# SCH_Schematic-PCB-FC-TD_2026-05-04.net
KiCad netlist of a schematic drawn in EasyEDA
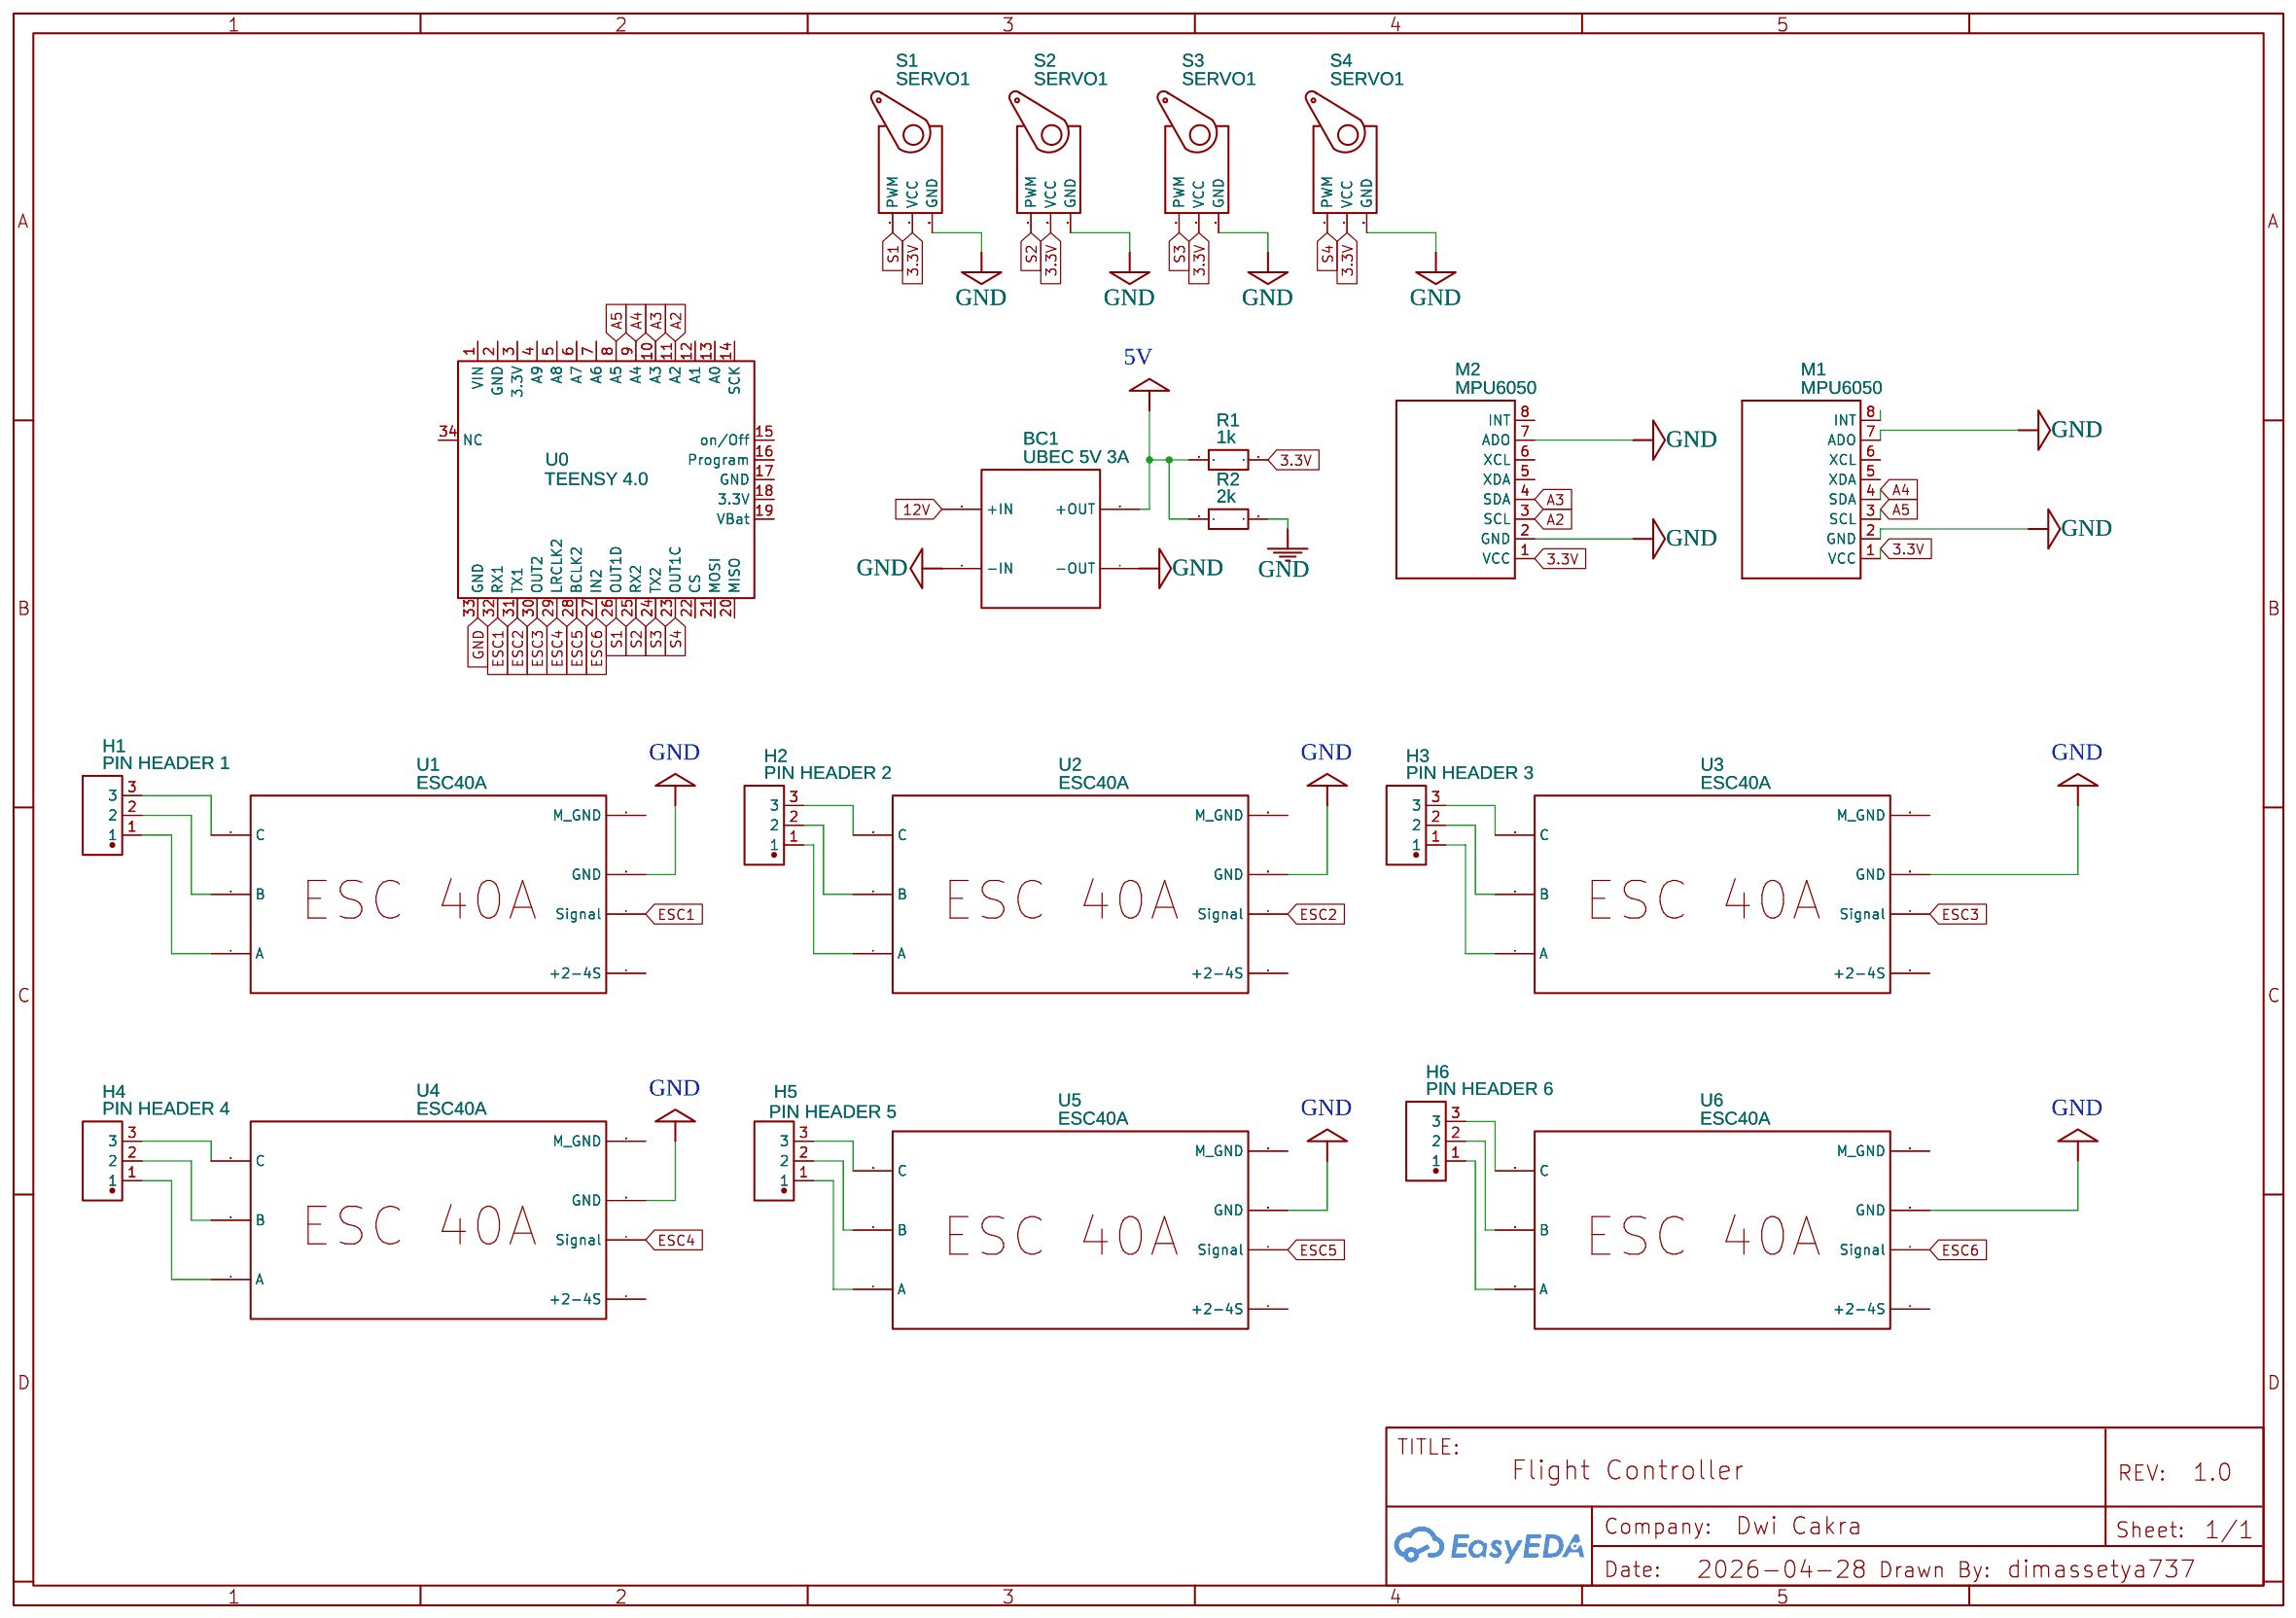
[diagram p0: schematic sheet]

(export (version "E")
  (design (tool "Eeschema 10.0.6"))
  (components
    (comp (ref "BC1") (value "UBEC 5V 3A") (libsource (lib "") (part "UBEC 5V 3A")))
    (comp (ref "H1")
      (value "PIN HEADER 1")
      (fields
        (field (name "Manufacturer Part") "HX PH254-01-03-Z-L11.5 pcb pin header")
        (field (name "Manufacturer") "hanxia(韩下)")
      )
      (libsource (lib "") (part "HX PH254-01-03-Z-L11.5 PCB PIN HEADER"))
    )
    (comp (ref "H2")
      (value "PIN HEADER 2")
      (fields
        (field (name "Manufacturer Part") "HX PH254-01-03-Z-L11.5 pcb pin header")
        (field (name "Manufacturer") "hanxia(韩下)")
      )
      (libsource (lib "") (part "HX PH254-01-03-Z-L11.5 PCB PIN HEADER"))
    )
    (comp (ref "H3")
      (value "PIN HEADER 3")
      (fields
        (field (name "Manufacturer Part") "HX PH254-01-03-Z-L11.5 pcb pin header")
        (field (name "Manufacturer") "hanxia(韩下)")
      )
      (libsource (lib "") (part "HX PH254-01-03-Z-L11.5 PCB PIN HEADER"))
    )
    (comp (ref "H4")
      (value "PIN HEADER 4")
      (fields
        (field (name "Manufacturer Part") "HX PH254-01-03-Z-L11.5 pcb pin header")
        (field (name "Manufacturer") "hanxia(韩下)")
      )
      (libsource (lib "") (part "HX PH254-01-03-Z-L11.5 PCB PIN HEADER"))
    )
    (comp (ref "H5")
      (value "PIN HEADER 5")
      (fields
        (field (name "Manufacturer Part") "HX PH254-01-03-Z-L11.5 pcb pin header")
        (field (name "Manufacturer") "hanxia(韩下)")
      )
      (libsource (lib "") (part "HX PH254-01-03-Z-L11.5 PCB PIN HEADER"))
    )
    (comp (ref "H6")
      (value "PIN HEADER 6")
      (fields
        (field (name "Manufacturer Part") "HX PH254-01-03-Z-L11.5 pcb pin header")
        (field (name "Manufacturer") "hanxia(韩下)")
      )
      (libsource (lib "") (part "HX PH254-01-03-Z-L11.5 PCB PIN HEADER"))
    )
    (comp (ref "M1") (value "MPU6050") (libsource (lib "") (part "MPU6050")))
    (comp (ref "M2") (value "MPU6050") (libsource (lib "") (part "MPU6050")))
    (comp (ref "R1")
      (value "1k")
      (fields (field (name "Manufacturer Part") "贴片电阻ChipResistors"))
      (libsource (lib "") (part "贴片电阻CHIPRESISTORS"))
    )
    (comp (ref "R2")
      (value "2k")
      (fields (field (name "Manufacturer Part") "贴片电阻ChipResistors"))
      (libsource (lib "") (part "贴片电阻CHIPRESISTORS"))
    )
    (comp (ref "S1") (value "SERVO1") (libsource (lib "") (part "SERVO MG90S")))
    (comp (ref "S2") (value "SERVO1") (libsource (lib "") (part "SERVO MG90S")))
    (comp (ref "S3") (value "SERVO1") (libsource (lib "") (part "SERVO MG90S")))
    (comp (ref "S4") (value "SERVO1") (libsource (lib "") (part "SERVO MG90S")))
    (comp (ref "U0")
      (value "TEENSY 4.0")
      (fields (field (name "Manufacturer Part") "Teensy 4.0"))
      (libsource (lib "") (part "TEENSY 4.0"))
    )
    (comp (ref "U1") (value "ESC40A") (libsource (lib "") (part "ESC40A")))
    (comp (ref "U2") (value "ESC40A") (libsource (lib "") (part "ESC40A")))
    (comp (ref "U3") (value "ESC40A") (libsource (lib "") (part "ESC40A")))
    (comp (ref "U4") (value "ESC40A") (libsource (lib "") (part "ESC40A")))
    (comp (ref "U5") (value "ESC40A") (libsource (lib "") (part "ESC40A_1")))
    (comp (ref "U6") (value "ESC40A") (libsource (lib "") (part "ESC40A_1")))
  )
  (nets
    (net (code "1") (name "3.3V") (class "Default")
      (node (ref "M1") (pin "1") (pinfunction "VCC_1") (pintype "bidirectional"))
      (node (ref "M2") (pin "1") (pinfunction "VCC_1") (pintype "bidirectional"))
      (node (ref "R1") (pin "2") (pinfunction "2_2") (pintype "unspecified"))
      (node (ref "S1") (pin "VCC") (pinfunction "VCC_VCC") (pintype "unspecified"))
      (node (ref "S2") (pin "VCC") (pinfunction "VCC_VCC") (pintype "unspecified"))
      (node (ref "S3") (pin "VCC") (pinfunction "VCC_VCC") (pintype "unspecified"))
      (node (ref "S4") (pin "VCC") (pinfunction "VCC_VCC") (pintype "unspecified"))
    )
    (net (code "2") (name "5V") (class "Default")
      (node (ref "BC1") (pin "3") (pinfunction "+OUT_3") (pintype "unspecified"))
      (node (ref "R1") (pin "1") (pinfunction "1_1") (pintype "unspecified"))
      (node (ref "R2") (pin "1") (pinfunction "1_1") (pintype "unspecified"))
    )
    (net (code "3") (name "12V") (class "Default")
      (node (ref "BC1") (pin "2") (pinfunction "+IN_2") (pintype "unspecified"))
    )
    (net (code "4") (name "A2") (class "Default")
      (node (ref "M2") (pin "3") (pinfunction "SCL_3") (pintype "bidirectional"))
      (node (ref "U0") (pin "11") (pinfunction "A2_11") (pintype "unspecified"))
    )
    (net (code "5") (name "A3") (class "Default")
      (node (ref "M2") (pin "4") (pinfunction "SDA_4") (pintype "bidirectional"))
      (node (ref "U0") (pin "10") (pinfunction "A3_10") (pintype "unspecified"))
    )
    (net (code "6") (name "A4") (class "Default")
      (node (ref "M1") (pin "4") (pinfunction "SDA_4") (pintype "bidirectional"))
      (node (ref "U0") (pin "9") (pinfunction "A4_9") (pintype "unspecified"))
    )
    (net (code "7") (name "A5") (class "Default")
      (node (ref "M1") (pin "3") (pinfunction "SCL_3") (pintype "bidirectional"))
      (node (ref "U0") (pin "8") (pinfunction "A5_8") (pintype "unspecified"))
    )
    (net (code "8") (name "ESC1") (class "Default")
      (node (ref "U0") (pin "32") (pinfunction "RX1_32") (pintype "unspecified"))
      (node (ref "U1") (pin "7") (pinfunction "Signal_7") (pintype "unspecified"))
    )
    (net (code "9") (name "ESC2") (class "Default")
      (node (ref "U0") (pin "31") (pinfunction "TX1_31") (pintype "unspecified"))
      (node (ref "U2") (pin "7") (pinfunction "Signal_7") (pintype "unspecified"))
    )
    (net (code "10") (name "ESC3") (class "Default")
      (node (ref "U0") (pin "30") (pinfunction "OUT2_30") (pintype "unspecified"))
      (node (ref "U3") (pin "7") (pinfunction "Signal_7") (pintype "unspecified"))
    )
    (net (code "11") (name "ESC4") (class "Default")
      (node (ref "U0") (pin "29") (pinfunction "LRCLK2_29") (pintype "unspecified"))
      (node (ref "U4") (pin "7") (pinfunction "Signal_7") (pintype "unspecified"))
    )
    (net (code "12") (name "ESC5") (class "Default")
      (node (ref "U0") (pin "28") (pinfunction "BCLK2_28") (pintype "unspecified"))
      (node (ref "U5") (pin "7") (pinfunction "Signal_7") (pintype "unspecified"))
    )
    (net (code "13") (name "ESC6") (class "Default")
      (node (ref "U0") (pin "27") (pinfunction "IN2_27") (pintype "unspecified"))
      (node (ref "U6") (pin "7") (pinfunction "Signal_7") (pintype "unspecified"))
    )
    (net (code "14") (name "GND") (class "Default")
      (node (ref "BC1") (pin "1") (pinfunction "-IN_1") (pintype "unspecified"))
      (node (ref "BC1") (pin "4") (pinfunction "-OUT_4") (pintype "unspecified"))
      (node (ref "M1") (pin "2") (pinfunction "GND_2") (pintype "bidirectional"))
      (node (ref "M1") (pin "7") (pinfunction "ADO_7") (pintype "bidirectional"))
      (node (ref "M2") (pin "2") (pinfunction "GND_2") (pintype "bidirectional"))
      (node (ref "M2") (pin "7") (pinfunction "ADO_7") (pintype "bidirectional"))
      (node (ref "R2") (pin "2") (pinfunction "2_2") (pintype "unspecified"))
      (node (ref "S1") (pin "GND") (pinfunction "GND_GND") (pintype "unspecified"))
      (node (ref "S2") (pin "GND") (pinfunction "GND_GND") (pintype "unspecified"))
      (node (ref "S3") (pin "GND") (pinfunction "GND_GND") (pintype "unspecified"))
      (node (ref "S4") (pin "GND") (pinfunction "GND_GND") (pintype "unspecified"))
      (node (ref "U0") (pin "33") (pinfunction "GND_33") (pintype "unspecified"))
      (node (ref "U1") (pin "6") (pinfunction "GND_6") (pintype "unspecified"))
      (node (ref "U2") (pin "6") (pinfunction "GND_6") (pintype "unspecified"))
      (node (ref "U3") (pin "6") (pinfunction "GND_6") (pintype "unspecified"))
      (node (ref "U4") (pin "6") (pinfunction "GND_6") (pintype "unspecified"))
      (node (ref "U5") (pin "6") (pinfunction "GND_6") (pintype "unspecified"))
      (node (ref "U6") (pin "6") (pinfunction "GND_6") (pintype "unspecified"))
    )
    (net (code "15") (name "Net-(U1-A)") (class "Default")
      (node (ref "H1") (pin "1") (pinfunction "1_1") (pintype "unspecified"))
      (node (ref "U1") (pin "1") (pinfunction "A_1") (pintype "unspecified"))
    )
    (net (code "16") (name "Net-(U1-B)") (class "Default")
      (node (ref "H1") (pin "2") (pinfunction "2_2") (pintype "unspecified"))
      (node (ref "U1") (pin "2") (pinfunction "B_2") (pintype "unspecified"))
    )
    (net (code "17") (name "Net-(U1-C)") (class "Default")
      (node (ref "H1") (pin "3") (pinfunction "3_3") (pintype "unspecified"))
      (node (ref "U1") (pin "3") (pinfunction "C_3") (pintype "unspecified"))
    )
    (net (code "18") (name "Net-(U2-A)") (class "Default")
      (node (ref "H2") (pin "1") (pinfunction "1_1") (pintype "unspecified"))
      (node (ref "U2") (pin "1") (pinfunction "A_1") (pintype "unspecified"))
    )
    (net (code "19") (name "Net-(U2-B)") (class "Default")
      (node (ref "H2") (pin "2") (pinfunction "2_2") (pintype "unspecified"))
      (node (ref "U2") (pin "2") (pinfunction "B_2") (pintype "unspecified"))
    )
    (net (code "20") (name "Net-(U2-C)") (class "Default")
      (node (ref "H2") (pin "3") (pinfunction "3_3") (pintype "unspecified"))
      (node (ref "U2") (pin "3") (pinfunction "C_3") (pintype "unspecified"))
    )
    (net (code "21") (name "Net-(U3-A)") (class "Default")
      (node (ref "H3") (pin "1") (pinfunction "1_1") (pintype "unspecified"))
      (node (ref "U3") (pin "1") (pinfunction "A_1") (pintype "unspecified"))
    )
    (net (code "22") (name "Net-(U3-B)") (class "Default")
      (node (ref "H3") (pin "2") (pinfunction "2_2") (pintype "unspecified"))
      (node (ref "U3") (pin "2") (pinfunction "B_2") (pintype "unspecified"))
    )
    (net (code "23") (name "Net-(U3-C)") (class "Default")
      (node (ref "H3") (pin "3") (pinfunction "3_3") (pintype "unspecified"))
      (node (ref "U3") (pin "3") (pinfunction "C_3") (pintype "unspecified"))
    )
    (net (code "24") (name "Net-(U4-A)") (class "Default")
      (node (ref "H4") (pin "1") (pinfunction "1_1") (pintype "unspecified"))
      (node (ref "U4") (pin "1") (pinfunction "A_1") (pintype "unspecified"))
    )
    (net (code "25") (name "Net-(U4-B)") (class "Default")
      (node (ref "H4") (pin "2") (pinfunction "2_2") (pintype "unspecified"))
      (node (ref "U4") (pin "2") (pinfunction "B_2") (pintype "unspecified"))
    )
    (net (code "26") (name "Net-(U4-C)") (class "Default")
      (node (ref "H4") (pin "3") (pinfunction "3_3") (pintype "unspecified"))
      (node (ref "U4") (pin "3") (pinfunction "C_3") (pintype "unspecified"))
    )
    (net (code "27") (name "Net-(U5-A)") (class "Default")
      (node (ref "H5") (pin "1") (pinfunction "1_1") (pintype "unspecified"))
      (node (ref "U5") (pin "1") (pinfunction "A_1") (pintype "unspecified"))
    )
    (net (code "28") (name "Net-(U5-B)") (class "Default")
      (node (ref "H5") (pin "2") (pinfunction "2_2") (pintype "unspecified"))
      (node (ref "U5") (pin "2") (pinfunction "B_2") (pintype "unspecified"))
    )
    (net (code "29") (name "Net-(U5-C)") (class "Default")
      (node (ref "H5") (pin "3") (pinfunction "3_3") (pintype "unspecified"))
      (node (ref "U5") (pin "3") (pinfunction "C_3") (pintype "unspecified"))
    )
    (net (code "30") (name "Net-(U6-A)") (class "Default")
      (node (ref "H6") (pin "1") (pinfunction "1_1") (pintype "unspecified"))
      (node (ref "U6") (pin "1") (pinfunction "A_1") (pintype "unspecified"))
    )
    (net (code "31") (name "Net-(U6-B)") (class "Default")
      (node (ref "H6") (pin "2") (pinfunction "2_2") (pintype "unspecified"))
      (node (ref "U6") (pin "2") (pinfunction "B_2") (pintype "unspecified"))
    )
    (net (code "32") (name "Net-(U6-C)") (class "Default")
      (node (ref "H6") (pin "3") (pinfunction "3_3") (pintype "unspecified"))
      (node (ref "U6") (pin "3") (pinfunction "C_3") (pintype "unspecified"))
    )
    (net (code "33") (name "S1") (class "Default")
      (node (ref "S1") (pin "PWM") (pinfunction "PWM_PWM") (pintype "unspecified"))
      (node (ref "U0") (pin "26") (pinfunction "OUT1D_26") (pintype "unspecified"))
    )
    (net (code "34") (name "S2") (class "Default")
      (node (ref "S2") (pin "PWM") (pinfunction "PWM_PWM") (pintype "unspecified"))
      (node (ref "U0") (pin "25") (pinfunction "RX2_25") (pintype "unspecified"))
    )
    (net (code "35") (name "S3") (class "Default")
      (node (ref "S3") (pin "PWM") (pinfunction "PWM_PWM") (pintype "unspecified"))
      (node (ref "U0") (pin "24") (pinfunction "TX2_24") (pintype "unspecified"))
    )
    (net (code "36") (name "S4") (class "Default")
      (node (ref "S4") (pin "PWM") (pinfunction "PWM_PWM") (pintype "unspecified"))
      (node (ref "U0") (pin "23") (pinfunction "OUT1C_23") (pintype "unspecified"))
    )
    (net (code "37") (name "unconnected-(M1-INT-Pad8)") (class "Default")
      (node (ref "M1") (pin "8") (pinfunction "INT_8") (pintype "bidirectional"))
    )
    (net (code "38") (name "unconnected-(M1-XCL-Pad6)") (class "Default")
      (node (ref "M1") (pin "6") (pinfunction "XCL_6") (pintype "bidirectional"))
    )
    (net (code "39") (name "unconnected-(M1-XDA-Pad5)") (class "Default")
      (node (ref "M1") (pin "5") (pinfunction "XDA_5") (pintype "bidirectional"))
    )
    (net (code "40") (name "unconnected-(M2-INT-Pad8)") (class "Default")
      (node (ref "M2") (pin "8") (pinfunction "INT_8") (pintype "bidirectional"))
    )
    (net (code "41") (name "unconnected-(M2-XCL-Pad6)") (class "Default")
      (node (ref "M2") (pin "6") (pinfunction "XCL_6") (pintype "bidirectional"))
    )
    (net (code "42") (name "unconnected-(M2-XDA-Pad5)") (class "Default")
      (node (ref "M2") (pin "5") (pinfunction "XDA_5") (pintype "bidirectional"))
    )
    (net (code "43") (name "unconnected-(U0-3.3V-Pad3)") (class "Default")
      (node (ref "U0") (pin "3") (pinfunction "3.3V_3") (pintype "unspecified"))
    )
    (net (code "44") (name "unconnected-(U0-3.3V-Pad18)") (class "Default")
      (node (ref "U0") (pin "18") (pinfunction "3.3V_18") (pintype "unspecified"))
    )
    (net (code "45") (name "unconnected-(U0-A0-Pad13)") (class "Default")
      (node (ref "U0") (pin "13") (pinfunction "A0_13") (pintype "unspecified"))
    )
    (net (code "46") (name "unconnected-(U0-A1-Pad12)") (class "Default")
      (node (ref "U0") (pin "12") (pinfunction "A1_12") (pintype "unspecified"))
    )
    (net (code "47") (name "unconnected-(U0-A6-Pad7)") (class "Default")
      (node (ref "U0") (pin "7") (pinfunction "A6_7") (pintype "unspecified"))
    )
    (net (code "48") (name "unconnected-(U0-A7-Pad6)") (class "Default")
      (node (ref "U0") (pin "6") (pinfunction "A7_6") (pintype "unspecified"))
    )
    (net (code "49") (name "unconnected-(U0-A8-Pad5)") (class "Default")
      (node (ref "U0") (pin "5") (pinfunction "A8_5") (pintype "unspecified"))
    )
    (net (code "50") (name "unconnected-(U0-A9-Pad4)") (class "Default")
      (node (ref "U0") (pin "4") (pinfunction "A9_4") (pintype "unspecified"))
    )
    (net (code "51") (name "unconnected-(U0-CS-Pad22)") (class "Default")
      (node (ref "U0") (pin "22") (pinfunction "CS_22") (pintype "unspecified"))
    )
    (net (code "52") (name "unconnected-(U0-GND-Pad2)") (class "Default")
      (node (ref "U0") (pin "2") (pinfunction "GND_2") (pintype "unspecified"))
    )
    (net (code "53") (name "unconnected-(U0-GND-Pad17)") (class "Default")
      (node (ref "U0") (pin "17") (pinfunction "GND_17") (pintype "unspecified"))
    )
    (net (code "54") (name "unconnected-(U0-MISO-Pad20)") (class "Default")
      (node (ref "U0") (pin "20") (pinfunction "MISO_20") (pintype "unspecified"))
    )
    (net (code "55") (name "unconnected-(U0-MOSI-Pad21)") (class "Default")
      (node (ref "U0") (pin "21") (pinfunction "MOSI_21") (pintype "unspecified"))
    )
    (net (code "56") (name "unconnected-(U0-NC-Pad34)") (class "Default")
      (node (ref "U0") (pin "34") (pinfunction "NC_34") (pintype "unspecified"))
    )
    (net (code "57") (name "unconnected-(U0-Program-Pad16)") (class "Default")
      (node (ref "U0") (pin "16") (pinfunction "Program_16") (pintype "unspecified"))
    )
    (net (code "58") (name "unconnected-(U0-SCK-Pad14)") (class "Default")
      (node (ref "U0") (pin "14") (pinfunction "SCK_14") (pintype "unspecified"))
    )
    (net (code "59") (name "unconnected-(U0-VBat-Pad19)") (class "Default")
      (node (ref "U0") (pin "19") (pinfunction "VBat_19") (pintype "unspecified"))
    )
    (net (code "60") (name "unconnected-(U0-VIN-Pad1)") (class "Default")
      (node (ref "U0") (pin "1") (pinfunction "VIN_1") (pintype "unspecified"))
    )
    (net (code "61") (name "unconnected-(U0-on{slash}Off-Pad15)") (class "Default")
      (node (ref "U0") (pin "15") (pinfunction "on/Off_15") (pintype "unspecified"))
    )
    (net (code "62") (name "unconnected-(U1-+2-4S-Pad4)") (class "Default")
      (node (ref "U1") (pin "4") (pinfunction "+2-4S_4") (pintype "unspecified"))
    )
    (net (code "63") (name "unconnected-(U1-M_GND-Pad5)") (class "Default")
      (node (ref "U1") (pin "5") (pinfunction "M_GND_5") (pintype "unspecified"))
    )
    (net (code "64") (name "unconnected-(U2-+2-4S-Pad4)") (class "Default")
      (node (ref "U2") (pin "4") (pinfunction "+2-4S_4") (pintype "unspecified"))
    )
    (net (code "65") (name "unconnected-(U2-M_GND-Pad5)") (class "Default")
      (node (ref "U2") (pin "5") (pinfunction "M_GND_5") (pintype "unspecified"))
    )
    (net (code "66") (name "unconnected-(U3-+2-4S-Pad4)") (class "Default")
      (node (ref "U3") (pin "4") (pinfunction "+2-4S_4") (pintype "unspecified"))
    )
    (net (code "67") (name "unconnected-(U3-M_GND-Pad5)") (class "Default")
      (node (ref "U3") (pin "5") (pinfunction "M_GND_5") (pintype "unspecified"))
    )
    (net (code "68") (name "unconnected-(U4-+2-4S-Pad4)") (class "Default")
      (node (ref "U4") (pin "4") (pinfunction "+2-4S_4") (pintype "unspecified"))
    )
    (net (code "69") (name "unconnected-(U4-M_GND-Pad5)") (class "Default")
      (node (ref "U4") (pin "5") (pinfunction "M_GND_5") (pintype "unspecified"))
    )
    (net (code "70") (name "unconnected-(U5-+2-4S-Pad4)") (class "Default")
      (node (ref "U5") (pin "4") (pinfunction "+2-4S_4") (pintype "unspecified"))
    )
    (net (code "71") (name "unconnected-(U5-M_GND-Pad5)") (class "Default")
      (node (ref "U5") (pin "5") (pinfunction "M_GND_5") (pintype "unspecified"))
    )
    (net (code "72") (name "unconnected-(U6-+2-4S-Pad4)") (class "Default")
      (node (ref "U6") (pin "4") (pinfunction "+2-4S_4") (pintype "unspecified"))
    )
    (net (code "73") (name "unconnected-(U6-M_GND-Pad5)") (class "Default")
      (node (ref "U6") (pin "5") (pinfunction "M_GND_5") (pintype "unspecified"))
    )
  )
)
